# MCU.net
KiCad netlist of a schematic drawn in Altium Designer
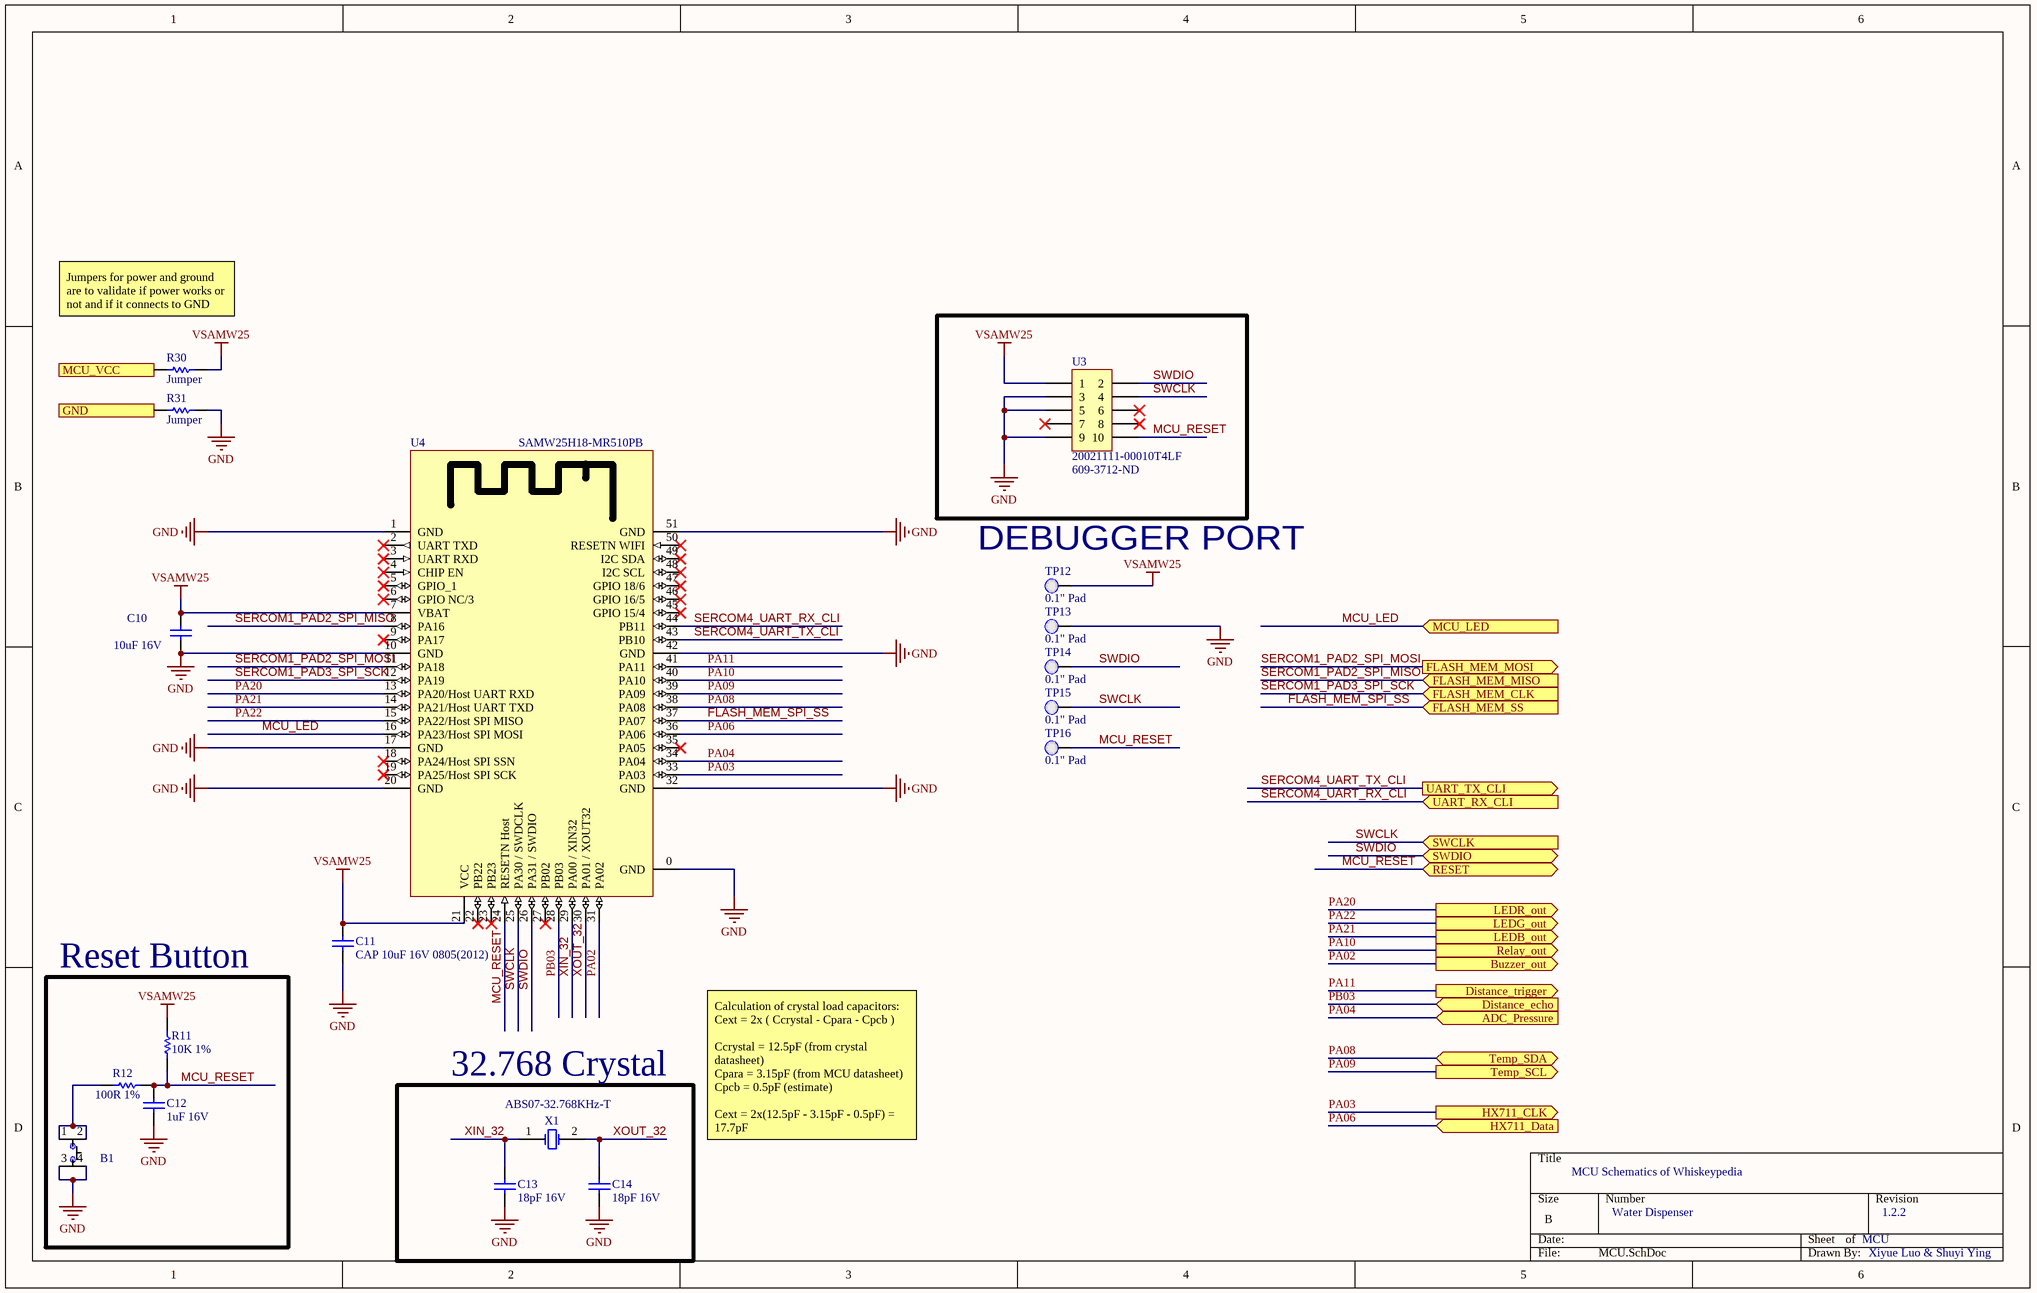
[diagram p0: MCU.SchDoc]

(export (version "E")
  (design (tool "Eeschema 10.0.6"))
  (components
    (comp (ref "B1")
      (value "PTS810 SJK 250 SMTR LFS")
      (footprint "PTS810 SJK 250 SMTR LFS")
      (description "SWITCH TACTILE SPST-NO 0.05A 16V Tactile Switch SPST-NO Top Actuated Surface Mount")
      (fields
        (field (name "MANUFACTURER") "ITT /  C&K Components")
        (field (name "MANUFACTURER PART NUMBER") "PTS810SJK250SMTRLFS")
      )
      (libsource (lib "Schematics") (part "PTS810 SJK 250 SMTR LFS"))
    )
    (comp (ref "C10")
      (value "10uF 16V")
      (footprint "CAPC0805(2012)145_N")
      (description "CAP 10uF 16V ±10% 0805 (2012 Metric) Thickness 1.45mm SMD")
      (fields (field (name "TOLERANCE") "Â±10%"))
      (libsource (lib "Altium Content Vault") (part "CAP"))
    )
    (comp (ref "C11")
      (value "CAP 10uF 16V 0805(2012)")
      (footprint "CAPC0805(2012)145_N")
      (description "CAP 10uF 16V ±10% 0805 (2012 Metric) Thickness 1.45mm SMD")
      (fields (field (name "TOLERANCE") "Â±10%"))
      (libsource (lib "Altium Content Vault") (part "CAP"))
    )
    (comp (ref "C12")
      (value "1uF 16V")
      (footprint "CAPC0603(1608)100_N")
      (description "CAP 1uF 16V ±5% 0603 (1608 Metric) Thickness 1mm SMD")
      (fields (field (name "TOLERANCE") "Â±5%"))
      (libsource (lib "Altium Content Vault") (part "CAP"))
    )
    (comp (ref "C13")
      (value "18pF 16V")
      (footprint "CAPC0603(1608)100_N")
      (description "CAP 18pF 16V ±5% 0603 (1608 Metric) Thickness 1mm SMD")
      (fields (field (name "TOLERANCE") "Â±5%"))
      (libsource (lib "Altium Content Vault") (part "CAP"))
    )
    (comp (ref "C14")
      (value "18pF 16V")
      (footprint "CAPC0603(1608)100_N")
      (description "CAP 18pF 16V ±5% 0603 (1608 Metric) Thickness 1mm SMD")
      (fields (field (name "TOLERANCE") "Â±5%"))
      (libsource (lib "Altium Content Vault") (part "CAP"))
    )
    (comp (ref "R11")
      (value "10K 1%")
      (footprint "RESC0603(1608)_N")
      (description "10K 0.1W 1% 0603 (1608 Metric)  SMD")
      (fields (field (name "POWER") "0.1 W") (field (name "TOLERANCE") "1 %"))
      (libsource (lib "Altium Content Vault") (part "RES"))
    )
    (comp (ref "R12")
      (value "100R 1%")
      (footprint "RESC0603(1608)_N")
      (description "100R 0.1W 1% 0603 (1608 Metric)  SMD")
      (fields (field (name "TOLERANCE") "1 %") (field (name "POWER") "0.1 W"))
      (libsource (lib "Altium Content Vault") (part "RES"))
    )
    (comp (ref "R30")
      (value "Jumper")
      (footprint "RESC0805(2012)_N")
      (description "Jumper 0805 (2012 Metric)")
      (fields (field (name "TOLERANCE") "None"))
      (libsource (lib "Altium Content Vault") (part "RES"))
    )
    (comp (ref "R31")
      (value "Jumper")
      (footprint "RESC0805(2012)_N")
      (description "Jumper 0805 (2012 Metric)")
      (fields (field (name "TOLERANCE") "None"))
      (libsource (lib "Altium Content Vault") (part "RES"))
    )
    (comp (ref "TP12")
      (value "0.1\" Pad")
      (footprint "PCBComponent")
      (libsource (lib "Components - 12.02.20 - 18.05") (part "0.1{dblquote} Pad-A.4"))
    )
    (comp (ref "TP13")
      (value "0.1\" Pad")
      (footprint "PCBComponent")
      (libsource (lib "Components - 12.02.20 - 18.05") (part "0.1{dblquote} Pad-A.4"))
    )
    (comp (ref "TP14")
      (value "0.1\" Pad")
      (footprint "PCBComponent")
      (libsource (lib "Components - 12.02.20 - 18.05") (part "0.1{dblquote} Pad-A.4"))
    )
    (comp (ref "TP15")
      (value "0.1\" Pad")
      (footprint "PCBComponent")
      (libsource (lib "Components - 12.02.20 - 18.05") (part "0.1{dblquote} Pad-A.4"))
    )
    (comp (ref "TP16")
      (value "0.1\" Pad")
      (footprint "PCBComponent")
      (libsource (lib "Components - 12.02.20 - 18.05") (part "0.1{dblquote} Pad-A.4"))
    )
    (comp (ref "U3")
      (value "20021111-00010T4LF")
      (footprint "20021111-00010T4LF")
      (description "CONN HEADER 10POS UNSHD VERT T/H")
      (fields
        (field (name "MANUFACTURER") "Amphenol / FCI")
        (field (name "SUPPLIER PART NUMBER 1") "609-3712-ND")
      )
      (libsource (lib "Schematics") (part "20021111-00010T4LF"))
    )
    (comp (ref "U4")
      (value "SAMW25H18-MR510PB")
      (footprint "SAMW25H18-MR510PB")
      (description "RF TXRX MODULE WIFI TRACE ANT")
      (fields
        (field (name "MANUFACTURER") "Atmel")
        (field (name "MANUFACTURER PART NUMBER") "ATSAMW25H18-MR510PB")
      )
      (libsource (lib "Schematics") (part "SAMW25H18-MR510PB"))
    )
    (comp (ref "X1")
      (value "ABS07-32.768KHz-T")
      (footprint "ABRA-ABS07-2_V")
      (description "Crystal, 32.768 kHz, 12.5 pF, -40 to 85 degC, SMD Low Profile 3.2 x 1.5 x 0.9 mm, Tape and Reel")
      (fields (field (name "MANUFACTURER") "Abracon"))
      (libsource (lib "Altium Content Vault") (part "ABRA-ABS07-2"))
    )
  )
  (nets
    (net (code "1") (name "/FLASH_MEM_SPI_SS") (class "Default")
      (node (ref "U4") (pin "37") (pinfunction "PA07_37") (pintype "bidirectional"))
    )
    (net (code "2") (name "/MCU_LED") (class "Default")
      (node (ref "U4") (pin "16") (pinfunction "PA23/Host_SPI_MOSI_16") (pintype "bidirectional"))
    )
    (net (code "3") (name "/MCU_RESET") (class "Default")
      (node (ref "C12") (pin "2") (pinfunction "2_2") (pintype "passive"))
      (node (ref "R11") (pin "1") (pinfunction "1_1") (pintype "passive"))
      (node (ref "R12") (pin "2") (pinfunction "2_2") (pintype "passive"))
      (node (ref "TP16") (pin "1") (pinfunction "PAD_1") (pintype "passive"))
      (node (ref "U3") (pin "10") (pinfunction "10_10") (pintype "passive"))
      (node (ref "U4") (pin "24") (pinfunction "RESETN_Host_24") (pintype "input"))
    )
    (net (code "4") (name "/MCU_VCC") (class "Default")
      (node (ref "R30") (pin "1") (pinfunction "1_1") (pintype "passive"))
    )
    (net (code "5") (name "/PA02") (class "Default")
      (node (ref "U4") (pin "31") (pinfunction "PA02_31") (pintype "bidirectional"))
    )
    (net (code "6") (name "/PA03") (class "Default")
      (node (ref "U4") (pin "33") (pinfunction "PA03_33") (pintype "bidirectional"))
    )
    (net (code "7") (name "/PA04") (class "Default")
      (node (ref "U4") (pin "34") (pinfunction "PA04_34") (pintype "bidirectional"))
    )
    (net (code "8") (name "/PA06") (class "Default")
      (node (ref "U4") (pin "36") (pinfunction "PA06_36") (pintype "bidirectional"))
    )
    (net (code "9") (name "/PA08") (class "Default")
      (node (ref "U4") (pin "38") (pinfunction "PA08_38") (pintype "bidirectional"))
    )
    (net (code "10") (name "/PA09") (class "Default")
      (node (ref "U4") (pin "39") (pinfunction "PA09_39") (pintype "bidirectional"))
    )
    (net (code "11") (name "/PA10") (class "Default")
      (node (ref "U4") (pin "40") (pinfunction "PA10_40") (pintype "bidirectional"))
    )
    (net (code "12") (name "/PA11") (class "Default")
      (node (ref "U4") (pin "41") (pinfunction "PA11_41") (pintype "bidirectional"))
    )
    (net (code "13") (name "/PA20") (class "Default")
      (node (ref "U4") (pin "13") (pinfunction "PA20/Host_UART_RXD_13") (pintype "bidirectional"))
    )
    (net (code "14") (name "/PA21") (class "Default")
      (node (ref "U4") (pin "14") (pinfunction "PA21/Host_UART_TXD_14") (pintype "bidirectional"))
    )
    (net (code "15") (name "/PA22") (class "Default")
      (node (ref "U4") (pin "15") (pinfunction "PA22/Host_SPI_MISO_15") (pintype "bidirectional"))
    )
    (net (code "16") (name "/PB03") (class "Default")
      (node (ref "U4") (pin "28") (pinfunction "PB03_28") (pintype "bidirectional"))
    )
    (net (code "17") (name "/SERCOM1_PAD2_SPI_MISO") (class "Default")
      (node (ref "U4") (pin "8") (pinfunction "PA16_8") (pintype "bidirectional"))
    )
    (net (code "18") (name "/SERCOM1_PAD2_SPI_MOSI") (class "Default")
      (node (ref "U4") (pin "11") (pinfunction "PA18_11") (pintype "bidirectional"))
    )
    (net (code "19") (name "/SERCOM1_PAD3_SPI_SCK") (class "Default")
      (node (ref "U4") (pin "12") (pinfunction "PA19_12") (pintype "bidirectional"))
    )
    (net (code "20") (name "/SERCOM4_UART_RX_CLI") (class "Default")
      (node (ref "U4") (pin "44") (pinfunction "PB11_44") (pintype "bidirectional"))
    )
    (net (code "21") (name "/SERCOM4_UART_TX_CLI") (class "Default")
      (node (ref "U4") (pin "43") (pinfunction "PB10_43") (pintype "bidirectional"))
    )
    (net (code "22") (name "/SWCLK") (class "Default")
      (node (ref "TP15") (pin "1") (pinfunction "PAD_1") (pintype "passive"))
      (node (ref "U3") (pin "4") (pinfunction "4_4") (pintype "passive"))
      (node (ref "U4") (pin "25") (pinfunction "PA30_/_SWDCLK_25") (pintype "bidirectional"))
    )
    (net (code "23") (name "/SWDIO") (class "Default")
      (node (ref "TP14") (pin "1") (pinfunction "PAD_1") (pintype "passive"))
      (node (ref "U3") (pin "2") (pinfunction "2_2") (pintype "passive"))
      (node (ref "U4") (pin "26") (pinfunction "PA31_/_SWDIO_26") (pintype "bidirectional"))
    )
    (net (code "24") (name "/XIN_32") (class "Default")
      (node (ref "C13") (pin "2") (pinfunction "2_2") (pintype "passive"))
      (node (ref "U4") (pin "29") (pinfunction "PA00_/_XIN32_29") (pintype "bidirectional"))
      (node (ref "X1") (pin "1") (pinfunction "X1_1") (pintype "passive"))
    )
    (net (code "25") (name "/XOUT_32") (class "Default")
      (node (ref "C14") (pin "2") (pinfunction "2_2") (pintype "passive"))
      (node (ref "U4") (pin "30") (pinfunction "PA01_/_XOUT32_30") (pintype "bidirectional"))
      (node (ref "X1") (pin "2") (pinfunction "X2_2") (pintype "passive"))
    )
    (net (code "26") (name "GND") (class "Default")
      (node (ref "B1") (pin "3") (pinfunction "3_3") (pintype "power_in"))
      (node (ref "B1") (pin "4") (pinfunction "4_4") (pintype "power_in"))
      (node (ref "C10") (pin "1") (pinfunction "1_1") (pintype "passive"))
      (node (ref "C11") (pin "1") (pinfunction "1_1") (pintype "passive"))
      (node (ref "C12") (pin "1") (pinfunction "1_1") (pintype "passive"))
      (node (ref "C13") (pin "1") (pinfunction "1_1") (pintype "passive"))
      (node (ref "C14") (pin "1") (pinfunction "1_1") (pintype "passive"))
      (node (ref "R31") (pin "1") (pinfunction "1_1") (pintype "passive"))
      (node (ref "R31") (pin "2") (pinfunction "2_2") (pintype "passive"))
      (node (ref "TP13") (pin "1") (pinfunction "PAD_1") (pintype "passive"))
      (node (ref "U3") (pin "3") (pinfunction "3_3") (pintype "passive"))
      (node (ref "U3") (pin "5") (pinfunction "5_5") (pintype "passive"))
      (node (ref "U3") (pin "9") (pinfunction "9_9") (pintype "passive"))
      (node (ref "U4") (pin "0") (pinfunction "GND_0") (pintype "power_in"))
      (node (ref "U4") (pin "1") (pinfunction "GND_1") (pintype "power_in"))
      (node (ref "U4") (pin "10") (pinfunction "GND_10") (pintype "power_in"))
      (node (ref "U4") (pin "17") (pinfunction "GND_17") (pintype "power_in"))
      (node (ref "U4") (pin "20") (pinfunction "GND_20") (pintype "power_in"))
      (node (ref "U4") (pin "32") (pinfunction "GND_32") (pintype "power_in"))
      (node (ref "U4") (pin "42") (pinfunction "GND_42") (pintype "power_in"))
      (node (ref "U4") (pin "51") (pinfunction "GND_51") (pintype "power_in"))
    )
    (net (code "27") (name "Net-(B1-Pad1)") (class "Default")
      (node (ref "B1") (pin "1") (pinfunction "1_1") (pintype "power_in"))
      (node (ref "B1") (pin "2") (pinfunction "2_2") (pintype "power_in"))
      (node (ref "R12") (pin "1") (pinfunction "1_1") (pintype "passive"))
    )
    (net (code "28") (name "VSAMW25") (class "Default")
      (node (ref "C10") (pin "2") (pinfunction "2_2") (pintype "passive"))
      (node (ref "C11") (pin "2") (pinfunction "2_2") (pintype "passive"))
      (node (ref "R11") (pin "2") (pinfunction "2_2") (pintype "passive"))
      (node (ref "R30") (pin "2") (pinfunction "2_2") (pintype "passive"))
      (node (ref "TP12") (pin "1") (pinfunction "PAD_1") (pintype "passive"))
      (node (ref "U3") (pin "1") (pinfunction "1_1") (pintype "passive"))
      (node (ref "U4") (pin "21") (pinfunction "VCC_21") (pintype "power_in"))
      (node (ref "U4") (pin "7") (pinfunction "VBAT_7") (pintype "power_in"))
    )
    (net (code "29") (name "unconnected-(U3-Pad6)") (class "Default")
      (node (ref "U3") (pin "6") (pinfunction "6_6") (pintype "passive+no_connect"))
    )
    (net (code "30") (name "unconnected-(U3-Pad7)") (class "Default")
      (node (ref "U3") (pin "7") (pinfunction "7_7") (pintype "passive+no_connect"))
    )
    (net (code "31") (name "unconnected-(U3-Pad8)") (class "Default")
      (node (ref "U3") (pin "8") (pinfunction "8_8") (pintype "passive+no_connect"))
    )
    (net (code "32") (name "unconnected-(U4-CHIP_EN-Pad4)") (class "Default")
      (node (ref "U4") (pin "4") (pinfunction "CHIP_EN_4") (pintype "input+no_connect"))
    )
    (net (code "33") (name "unconnected-(U4-GPIO_1-Pad5)") (class "Default")
      (node (ref "U4") (pin "5") (pinfunction "GPIO_1_5") (pintype "bidirectional+no_connect"))
    )
    (net (code "34") (name "unconnected-(U4-GPIO_15{slash}4-Pad45)") (class "Default")
      (node (ref "U4") (pin "45") (pinfunction "GPIO_15/4_45") (pintype "bidirectional+no_connect"))
    )
    (net (code "35") (name "unconnected-(U4-GPIO_16{slash}5-Pad46)") (class "Default")
      (node (ref "U4") (pin "46") (pinfunction "GPIO_16/5_46") (pintype "bidirectional+no_connect"))
    )
    (net (code "36") (name "unconnected-(U4-GPIO_18{slash}6-Pad47)") (class "Default")
      (node (ref "U4") (pin "47") (pinfunction "GPIO_18/6_47") (pintype "bidirectional+no_connect"))
    )
    (net (code "37") (name "unconnected-(U4-GPIO_NC{slash}3-Pad6)") (class "Default")
      (node (ref "U4") (pin "6") (pinfunction "GPIO_NC/3_6") (pintype "bidirectional+no_connect"))
    )
    (net (code "38") (name "unconnected-(U4-I2C_SCL-Pad48)") (class "Default")
      (node (ref "U4") (pin "48") (pinfunction "I2C_SCL_48") (pintype "bidirectional+no_connect"))
    )
    (net (code "39") (name "unconnected-(U4-I2C_SDA-Pad49)") (class "Default")
      (node (ref "U4") (pin "49") (pinfunction "I2C_SDA_49") (pintype "bidirectional+no_connect"))
    )
    (net (code "40") (name "unconnected-(U4-PA05-Pad35)") (class "Default")
      (node (ref "U4") (pin "35") (pinfunction "PA05_35") (pintype "bidirectional+no_connect"))
    )
    (net (code "41") (name "unconnected-(U4-PA17-Pad9)") (class "Default")
      (node (ref "U4") (pin "9") (pinfunction "PA17_9") (pintype "bidirectional+no_connect"))
    )
    (net (code "42") (name "unconnected-(U4-PA24{slash}Host_SPI_SSN-Pad18)") (class "Default")
      (node (ref "U4") (pin "18") (pinfunction "PA24/Host_SPI_SSN_18") (pintype "bidirectional+no_connect"))
    )
    (net (code "43") (name "unconnected-(U4-PA25{slash}Host_SPI_SCK-Pad19)") (class "Default")
      (node (ref "U4") (pin "19") (pinfunction "PA25/Host_SPI_SCK_19") (pintype "bidirectional+no_connect"))
    )
    (net (code "44") (name "unconnected-(U4-PB02-Pad27)") (class "Default")
      (node (ref "U4") (pin "27") (pinfunction "PB02_27") (pintype "bidirectional+no_connect"))
    )
    (net (code "45") (name "unconnected-(U4-PB22-Pad22)") (class "Default")
      (node (ref "U4") (pin "22") (pinfunction "PB22_22") (pintype "bidirectional+no_connect"))
    )
    (net (code "46") (name "unconnected-(U4-PB23-Pad23)") (class "Default")
      (node (ref "U4") (pin "23") (pinfunction "PB23_23") (pintype "bidirectional+no_connect"))
    )
    (net (code "47") (name "unconnected-(U4-RESETN_WIFI-Pad50)") (class "Default")
      (node (ref "U4") (pin "50") (pinfunction "RESETN_WIFI_50") (pintype "input+no_connect"))
    )
    (net (code "48") (name "unconnected-(U4-UART_RXD-Pad3)") (class "Default")
      (node (ref "U4") (pin "3") (pinfunction "UART_RXD_3") (pintype "input+no_connect"))
    )
    (net (code "49") (name "unconnected-(U4-UART_TXD-Pad2)") (class "Default")
      (node (ref "U4") (pin "2") (pinfunction "UART_TXD_2") (pintype "output+no_connect"))
    )
  )
)
